# Sheet1.net
KiCad netlist of a schematic drawn in Altium Designer
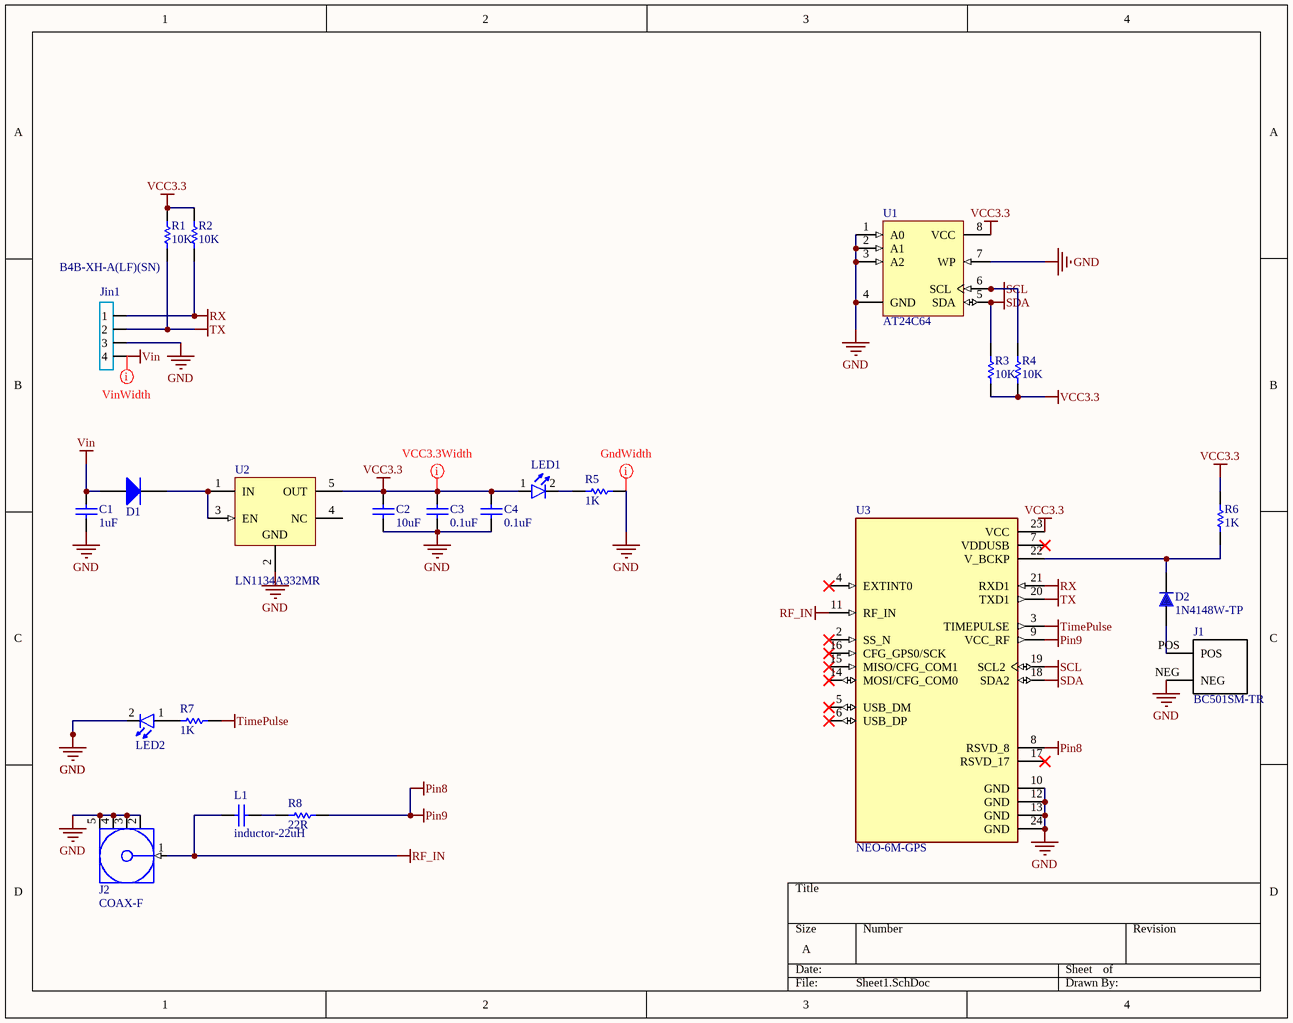
[diagram p0: Sheet1.SchDoc]

(export (version "E")
  (design (tool "Eeschema 10.0.6"))
  (components
    (comp (ref "C1")
      (value "1uF")
      (footprint "CAPC4817X12N")
      (description "CAP 1206")
      (fields (field (name "DESIGNER") "Abbas Basereh"))
      (libsource (lib "General 1") (part "CAP SMD 1206"))
    )
    (comp (ref "C2")
      (value "10uF")
      (footprint "CAPC4817X12N")
      (description "CAP 1206")
      (fields (field (name "DESIGNER") "Abbas Basereh"))
      (libsource (lib "General 1") (part "CAP SMD 1206"))
    )
    (comp (ref "C3")
      (value "0.1uF")
      (footprint "CAPC4817X12N")
      (description "CAP 1206")
      (fields (field (name "DESIGNER") "Abbas Basereh"))
      (libsource (lib "General 1") (part "CAP SMD 1206"))
    )
    (comp (ref "C4")
      (value "0.1uF")
      (footprint "CAPC4817X12N")
      (description "CAP 1206")
      (fields (field (name "DESIGNER") "Abbas Basereh"))
      (libsource (lib "General 1") (part "CAP SMD 1206"))
    )
    (comp (ref "D1")
      (value "1n4007")
      (footprint "DIOM4629X24N")
      (description "Standard Rectifiers")
      (fields (field (name "MANUFACTURER") "DC COMPONENTS") (field (name "DESIGNER") "Abbas Basereh"))
      (libsource (lib "General 1") (part "1n4007 SMD M7"))
    )
    (comp (ref "D2")
      (value "1N4148W-TP")
      (footprint "SOD123")
      (description "DIODE GEN PURP 100V 150MA SOD123")
      (fields (field (name "PUBLISHER") "Abbas Basereh"))
      (libsource (lib "General 1") (part "1N4148W-TP"))
    )
    (comp (ref "J1")
      (value "BC501SM-TR")
      (footprint "*MPD_BC501SM-TR_BC501SM-TR(Primary)")
      (libsource (lib "BC501SM-TR") (part "BC501SM-TR"))
    )
    (comp (ref "J2")
      (value "COAX-F")
      (footprint "MCX5.08-H5")
      (fields (field (name "PUBLISHER") "Altium Limited"))
      (libsource (lib "Miscellaneous Connectors") (part "COAX-F"))
    )
    (comp (ref "Jin1")
      (value "B4B-XH-A(LF)(SN)")
      (footprint "*JST_B4B-XH-A(LF)(SN)")
      (description "XH Series 4 Position 2.5 mm Pitch Through Hole Crimp Top Entry Shrouded Header")
      (fields (field (name "MF") "JST Sales") (field (name "MP") "B4B-XH-A_LF__SN_"))
      (libsource (lib "Socket_4_PIN_2-5mm_JST") (part "B4B-XH-A(LF)(SN)"))
    )
    (comp (ref "L1")
      (value "inductor-22uH")
      (footprint "IND1206")
      (description "TOTAL INDUCTOR SMD PACK")
      (fields (field (name "DESIGNER") "Abbas Basereh"))
      (libsource (lib "General 1") (part "INDUCTOR SMD PACKAGE"))
    )
    (comp (ref "LED1")
      (value "Red")
      (footprint "LED SMD 1206")
      (description "LED")
      (fields (field (name "DESIGNER") "Saeid Jorablo"))
      (libsource (lib "General 2") (part "LED"))
    )
    (comp (ref "LED2")
      (value "Red")
      (footprint "LED SMD 1206")
      (description "LED")
      (fields (field (name "DESIGNER") "Saeid Jorablo"))
      (libsource (lib "General 2") (part "LED"))
    )
    (comp (ref "R1")
      (value "10K")
      (footprint "RESC4817X04N")
      (description "RES 1206")
      (fields (field (name "DESIGNER") "Abbas Basereh"))
      (libsource (lib "General 1") (part "RES 1206 0.25W"))
    )
    (comp (ref "R2")
      (value "10K")
      (footprint "RESC4817X04N")
      (description "RES 1206")
      (fields (field (name "DESIGNER") "Abbas Basereh"))
      (libsource (lib "General 1") (part "RES 1206 0.25W"))
    )
    (comp (ref "R3")
      (value "10K")
      (footprint "RESC4817X04N")
      (description "RES 1206")
      (fields (field (name "DESIGNER") "Abbas Basereh"))
      (libsource (lib "General 1") (part "RES 1206 0.25W"))
    )
    (comp (ref "R4")
      (value "10K")
      (footprint "RESC4817X04N")
      (description "RES 1206")
      (fields (field (name "DESIGNER") "Abbas Basereh"))
      (libsource (lib "General 1") (part "RES 1206 0.25W"))
    )
    (comp (ref "R5")
      (value "1K")
      (footprint "RESC4817X04N")
      (description "RES 1206")
      (fields (field (name "DESIGNER") "Abbas Basereh"))
      (libsource (lib "General 1") (part "RES 1206 0.25W"))
    )
    (comp (ref "R6")
      (value "1K")
      (footprint "RESC4817X04N")
      (description "RES 1206")
      (fields (field (name "DESIGNER") "Abbas Basereh"))
      (libsource (lib "General 1") (part "RES 1206 0.25W"))
    )
    (comp (ref "R7")
      (value "1K")
      (footprint "RESC4817X04N")
      (description "RES 1206")
      (fields (field (name "DESIGNER") "Abbas Basereh"))
      (libsource (lib "General 1") (part "RES 1206 0.25W"))
    )
    (comp (ref "R8")
      (value "22R")
      (footprint "RESC4817X04N")
      (description "RES 1206")
      (fields (field (name "DESIGNER") "Abbas Basereh"))
      (libsource (lib "General 1") (part "RES 1206 0.25W"))
    )
    (comp (ref "U1")
      (value "AT24C64")
      (footprint "8S1_M")
      (description "1Kbit (128 x 8), 2-wire Bus Automotive Serial EEPROM with Write Protect, 2.5V, 8-Pin SOIC, Bulk")
      (libsource (lib "Atmel Serial EEPROM") (part "AT24C01BN-SP25-B"))
    )
    (comp (ref "U2")
      (value "LN1134A332MR")
      (footprint "MF05A_M")
      (description "Micropower, 150mA Low-Dropout CMOS Voltage Regulator, 5-pin SOT-23")
      (fields
        (field (name "PARTNUMBER") "LP5951MF-1.3")
        (field (name "MANUFACTURER") "National Semiconductor")
        (field (name "PUBLISHER") "Altium Limited")
      )
      (libsource (lib "NSC LDO") (part "LP5951MF-1.3"))
    )
    (comp (ref "U3")
      (value "NEO-6M-GPS")
      (footprint "XCVR_NEO-6M-GPS")
      (description "SMD GPS Module;")
      (fields (field (name "MF") "u-blox"))
      (libsource (lib "NEO-6M-GPS") (part "NEO-6M-GPS"))
    )
  )
  (nets
    (net (code "1") (name "GND") (class "Default")
      (node (ref "C1") (pin "1") (pinfunction "1_1") (pintype "passive"))
      (node (ref "C2") (pin "1") (pinfunction "1_1") (pintype "passive"))
      (node (ref "C3") (pin "1") (pinfunction "1_1") (pintype "passive"))
      (node (ref "C4") (pin "1") (pinfunction "1_1") (pintype "passive"))
      (node (ref "J1") (pin "NEG") (pinfunction "NEG_NEG") (pintype "passive"))
      (node (ref "J2") (pin "2") (pinfunction "GND_2") (pintype "power_in"))
      (node (ref "J2") (pin "3") (pinfunction "GND_3") (pintype "power_in"))
      (node (ref "J2") (pin "4") (pinfunction "GND_4") (pintype "power_in"))
      (node (ref "J2") (pin "5") (pinfunction "GND_5") (pintype "power_in"))
      (node (ref "Jin1") (pin "3") (pinfunction "3_3") (pintype "passive"))
      (node (ref "LED2") (pin "2") (pinfunction "K_2") (pintype "passive"))
      (node (ref "R5") (pin "2") (pinfunction "2_2") (pintype "passive"))
      (node (ref "U1") (pin "1") (pinfunction "A0_1") (pintype "input"))
      (node (ref "U1") (pin "2") (pinfunction "A1_2") (pintype "input"))
      (node (ref "U1") (pin "3") (pinfunction "A2_3") (pintype "input"))
      (node (ref "U1") (pin "4") (pinfunction "GND_4") (pintype "power_in"))
      (node (ref "U1") (pin "7") (pinfunction "WP_7") (pintype "input"))
      (node (ref "U2") (pin "2") (pinfunction "GND_2") (pintype "power_in"))
      (node (ref "U3") (pin "10") (pinfunction "GND_10") (pintype "power_in"))
      (node (ref "U3") (pin "12") (pinfunction "GND_12") (pintype "power_in"))
      (node (ref "U3") (pin "13") (pinfunction "GND_13") (pintype "power_in"))
      (node (ref "U3") (pin "24") (pinfunction "GND_24") (pintype "power_in"))
    )
    (net (code "2") (name "Net-(D1-K)") (class "Default")
      (node (ref "D1") (pin "2") (pinfunction "K_2") (pintype "passive"))
      (node (ref "U2") (pin "1") (pinfunction "IN_1") (pintype "power_in"))
      (node (ref "U2") (pin "3") (pinfunction "EN_3") (pintype "input"))
    )
    (net (code "3") (name "Net-(D2-Pad1)") (class "Default")
      (node (ref "D2") (pin "1") (pintype "passive"))
      (node (ref "J1") (pin "POS") (pinfunction "POS_POS") (pintype "passive"))
    )
    (net (code "4") (name "Net-(L1-Pad2)") (class "Default")
      (node (ref "L1") (pin "2") (pinfunction "2_2") (pintype "passive"))
      (node (ref "R8") (pin "1") (pinfunction "1_1") (pintype "passive"))
    )
    (net (code "5") (name "Net-(LED1-K)") (class "Default")
      (node (ref "LED1") (pin "2") (pinfunction "K_2") (pintype "passive"))
      (node (ref "R5") (pin "1") (pinfunction "1_1") (pintype "passive"))
    )
    (net (code "6") (name "Net-(LED2-A)") (class "Default")
      (node (ref "LED2") (pin "1") (pinfunction "A_1") (pintype "passive"))
      (node (ref "R7") (pin "1") (pinfunction "1_1") (pintype "passive"))
    )
    (net (code "7") (name "Net-(U3-V_BCKP)") (class "Default")
      (node (ref "D2") (pin "2") (pintype "passive"))
      (node (ref "R6") (pin "1") (pinfunction "1_1") (pintype "passive"))
      (node (ref "U3") (pin "22") (pinfunction "V_BCKP_22") (pintype "power_in"))
    )
    (net (code "8") (name "Pin8") (class "Default")
      (node (ref "R8") (pin "2") (pinfunction "2_2") (pintype "passive"))
      (node (ref "U3") (pin "8") (pinfunction "RSVD_8_8") (pintype "passive"))
      (node (ref "U3") (pin "9") (pinfunction "VCC_RF_9") (pintype "output"))
    )
    (net (code "9") (name "RF_IN") (class "Default")
      (node (ref "J2") (pin "1") (pinfunction "Signal_1") (pintype "input"))
      (node (ref "L1") (pin "1") (pinfunction "1_1") (pintype "passive"))
      (node (ref "U3") (pin "11") (pinfunction "RF_IN_11") (pintype "input"))
    )
    (net (code "10") (name "RX") (class "Default")
      (node (ref "Jin1") (pin "1") (pinfunction "1_1") (pintype "passive"))
      (node (ref "R2") (pin "1") (pinfunction "1_1") (pintype "passive"))
      (node (ref "U3") (pin "21") (pinfunction "RXD1_21") (pintype "input"))
    )
    (net (code "11") (name "SCL") (class "Default")
      (node (ref "R4") (pin "2") (pinfunction "2_2") (pintype "passive"))
      (node (ref "U1") (pin "6") (pinfunction "SCL_6") (pintype "input"))
      (node (ref "U3") (pin "19") (pinfunction "SCL2_19") (pintype "bidirectional"))
    )
    (net (code "12") (name "SDA") (class "Default")
      (node (ref "R3") (pin "2") (pinfunction "2_2") (pintype "passive"))
      (node (ref "U1") (pin "5") (pinfunction "SDA_5") (pintype "bidirectional"))
      (node (ref "U3") (pin "18") (pinfunction "SDA2_18") (pintype "bidirectional"))
    )
    (net (code "13") (name "TX") (class "Default")
      (node (ref "Jin1") (pin "2") (pinfunction "2_2") (pintype "passive"))
      (node (ref "R1") (pin "1") (pinfunction "1_1") (pintype "passive"))
      (node (ref "U3") (pin "20") (pinfunction "TXD1_20") (pintype "output"))
    )
    (net (code "14") (name "TimePulse") (class "Default")
      (node (ref "R7") (pin "2") (pinfunction "2_2") (pintype "passive"))
      (node (ref "U3") (pin "3") (pinfunction "TIMEPULSE_3") (pintype "output"))
    )
    (net (code "15") (name "VCC3.3") (class "Default")
      (node (ref "C2") (pin "2") (pinfunction "2_2") (pintype "passive"))
      (node (ref "C3") (pin "2") (pinfunction "2_2") (pintype "passive"))
      (node (ref "C4") (pin "2") (pinfunction "2_2") (pintype "passive"))
      (node (ref "LED1") (pin "1") (pinfunction "A_1") (pintype "passive"))
      (node (ref "R1") (pin "2") (pinfunction "2_2") (pintype "passive"))
      (node (ref "R2") (pin "2") (pinfunction "2_2") (pintype "passive"))
      (node (ref "R3") (pin "1") (pinfunction "1_1") (pintype "passive"))
      (node (ref "R4") (pin "1") (pinfunction "1_1") (pintype "passive"))
      (node (ref "R6") (pin "2") (pinfunction "2_2") (pintype "passive"))
      (node (ref "U1") (pin "8") (pinfunction "VCC_8") (pintype "power_in"))
      (node (ref "U2") (pin "5") (pinfunction "OUT_5") (pintype "power_in"))
      (node (ref "U3") (pin "23") (pinfunction "VCC_23") (pintype "power_in"))
    )
    (net (code "16") (name "Vin") (class "Default")
      (node (ref "C1") (pin "2") (pinfunction "2_2") (pintype "passive"))
      (node (ref "D1") (pin "1") (pinfunction "A_1") (pintype "passive"))
      (node (ref "Jin1") (pin "4") (pinfunction "4_4") (pintype "passive"))
    )
    (net (code "17") (name "unconnected-(U2-NC-Pad4)") (class "Default")
      (node (ref "U2") (pin "4") (pinfunction "NC_4") (pintype "passive"))
    )
    (net (code "18") (name "unconnected-(U3-CFG_GPS0{slash}SCK-Pad16)") (class "Default")
      (node (ref "U3") (pin "16") (pinfunction "CFG_GPS0/SCK_16") (pintype "input+no_connect"))
    )
    (net (code "19") (name "unconnected-(U3-EXTINT0-Pad4)") (class "Default")
      (node (ref "U3") (pin "4") (pinfunction "EXTINT0_4") (pintype "input+no_connect"))
    )
    (net (code "20") (name "unconnected-(U3-MISO{slash}CFG_COM1-Pad15)") (class "Default")
      (node (ref "U3") (pin "15") (pinfunction "MISO/CFG_COM1_15") (pintype "input+no_connect"))
    )
    (net (code "21") (name "unconnected-(U3-MOSI{slash}CFG_COM0-Pad14)") (class "Default")
      (node (ref "U3") (pin "14") (pinfunction "MOSI/CFG_COM0_14") (pintype "bidirectional+no_connect"))
    )
    (net (code "22") (name "unconnected-(U3-RSVD_17-Pad17)") (class "Default")
      (node (ref "U3") (pin "17") (pinfunction "RSVD_17_17") (pintype "passive+no_connect"))
    )
    (net (code "23") (name "unconnected-(U3-SS_N-Pad2)") (class "Default")
      (node (ref "U3") (pin "2") (pinfunction "SS_N_2") (pintype "input+no_connect"))
    )
    (net (code "24") (name "unconnected-(U3-USB_DM-Pad5)") (class "Default")
      (node (ref "U3") (pin "5") (pinfunction "USB_DM_5") (pintype "bidirectional+no_connect"))
    )
    (net (code "25") (name "unconnected-(U3-USB_DP-Pad6)") (class "Default")
      (node (ref "U3") (pin "6") (pinfunction "USB_DP_6") (pintype "bidirectional+no_connect"))
    )
    (net (code "26") (name "unconnected-(U3-VDDUSB-Pad7)") (class "Default")
      (node (ref "U3") (pin "7") (pinfunction "VDDUSB_7") (pintype "power_in+no_connect"))
    )
  )
)
